# ToneGeneratorSMD_V1viii.net
KiCad netlist of a schematic drawn in EAGLE
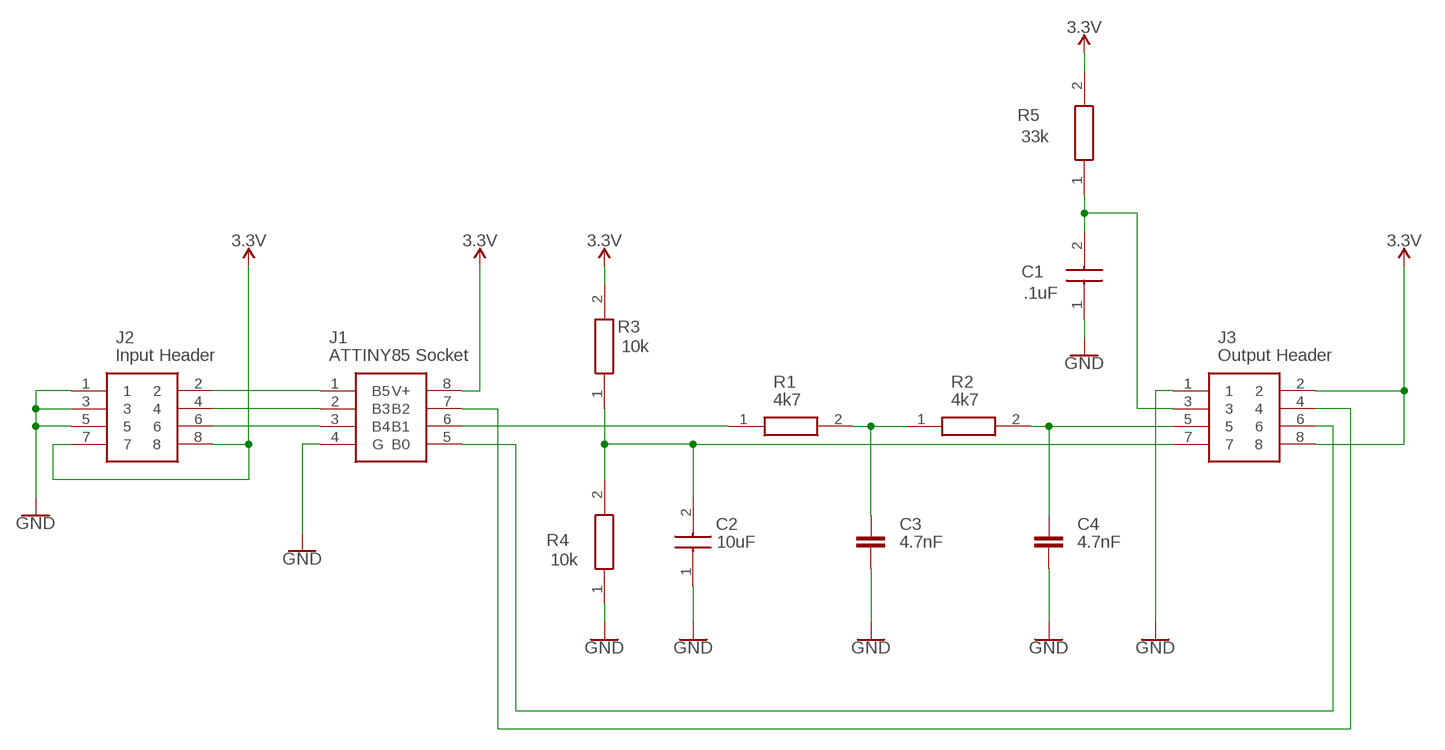
[diagram p0: schematic, sheet 1]

(export (version "E")
  (design (tool "Eeschema 10.0.6"))
  (components
    (comp (ref "C1")
      (value ".1uF")
      (footprint "eagle-import:CAPC2012X90N")
      (fields
        (field (name "MANUFACTURER_PART_NUMBER") "885012207098")
        (field (name "MOUSER_PART_NUMBER") "710-885012207098")
      )
      (libsource (lib "eagle-import") (part "885012207098"))
    )
    (comp (ref "C2")
      (value "10uF")
      (footprint "eagle-import:CAPC2012X145N")
      (fields
        (field (name "MANUFACTURER_PART_NUMBER") "GRM21BR61E106MA73L")
        (field (name "MOUSER_PART_NUMBER") "81-GRM21BR61E106MA3L")
      )
      (libsource (lib "eagle-import") (part "GRM21BR61E106MA73L"))
    )
    (comp (ref "C3")
      (value "4.7nF")
      (footprint "eagle-import:C0805")
      (libsource (lib "eagle-import") (part "C-EUC0805"))
    )
    (comp (ref "C4")
      (value "4.7nF")
      (footprint "eagle-import:C0805")
      (libsource (lib "eagle-import") (part "C-EUC0805"))
    )
    (comp (ref "J1")
      (value "ATTINY85 Socket")
      (footprint "eagle-import:2144430801670800")
      (fields
        (field (name "MANUFACTURER_PART_NUMBER") "214-44-308-01-670800")
        (field (name "MOUSER_PART_NUMBER") "575-4430801")
      )
      (libsource (lib "eagle-import") (part "214-44-308-01-670800"))
    )
    (comp (ref "J2")
      (value "Input Header")
      (footprint "eagle-import:878980826")
      (fields
        (field (name "MANUFACTURER_PART_NUMBER") "87898-0826")
        (field (name "MOUSER_PART_NUMBER") "538-87898-0826")
      )
      (libsource (lib "eagle-import") (part "87898-0826"))
    )
    (comp (ref "J3")
      (value "Output Header")
      (footprint "eagle-import:878980826")
      (fields
        (field (name "MANUFACTURER_PART_NUMBER") "87898-0826")
        (field (name "MOUSER_PART_NUMBER") "538-87898-0826")
      )
      (libsource (lib "eagle-import") (part "87898-0826"))
    )
    (comp (ref "R1")
      (value "4k7")
      (footprint "eagle-import:RESC2013X65N")
      (fields
        (field (name "MANUFACTURER_PART_NUMBER") "ERJ-6GEYJ472V")
        (field (name "MOUSER_PART_NUMBER") "667-ERJ-6GEYJ472V")
      )
      (libsource (lib "eagle-import") (part "ERJ-6GEYJ472V"))
    )
    (comp (ref "R2")
      (value "4k7")
      (footprint "eagle-import:RESC2013X65N")
      (fields
        (field (name "MANUFACTURER_PART_NUMBER") "ERJ-6GEYJ472V")
        (field (name "MOUSER_PART_NUMBER") "667-ERJ-6GEYJ472V")
      )
      (libsource (lib "eagle-import") (part "ERJ-6GEYJ472V"))
    )
    (comp (ref "R3")
      (value "10k")
      (footprint "eagle-import:RESC2013X65N")
      (fields
        (field (name "MANUFACTURER_PART_NUMBER") "ERJ-6GEYJ472V")
        (field (name "MOUSER_PART_NUMBER") "667-ERJ-6GEYJ472V")
      )
      (libsource (lib "eagle-import") (part "ERJ-6GEYJ472V"))
    )
    (comp (ref "R4")
      (value "10k")
      (footprint "eagle-import:RESC2013X65N")
      (fields
        (field (name "MANUFACTURER_PART_NUMBER") "ERJ-6GEYJ472V")
        (field (name "MOUSER_PART_NUMBER") "667-ERJ-6GEYJ472V")
      )
      (libsource (lib "eagle-import") (part "ERJ-6GEYJ472V"))
    )
    (comp (ref "R5")
      (value "33k")
      (footprint "eagle-import:RESC2013X65N")
      (fields
        (field (name "MANUFACTURER_PART_NUMBER") "ERJ-6GEYJ472V")
        (field (name "MOUSER_PART_NUMBER") "667-ERJ-6GEYJ472V")
      )
      (libsource (lib "eagle-import") (part "ERJ-6GEYJ472V"))
    )
  )
  (nets
    (net (code "1") (name "3.3V") (class "Default")
      (node (ref "J1") (pin "8") (pinfunction "V+_8") (pintype "bidirectional"))
      (node (ref "J2") (pin "7") (pinfunction "7_7") (pintype "bidirectional"))
      (node (ref "J2") (pin "8") (pinfunction "8_8") (pintype "bidirectional"))
      (node (ref "J3") (pin "2") (pinfunction "2_2") (pintype "bidirectional"))
      (node (ref "J3") (pin "8") (pinfunction "8_8") (pintype "bidirectional"))
      (node (ref "R3") (pin "2") (pinfunction "R2_2") (pintype "bidirectional"))
      (node (ref "R5") (pin "2") (pinfunction "R2_2") (pintype "bidirectional"))
    )
    (net (code "2") (name "GND") (class "Default")
      (node (ref "C1") (pin "1") (pinfunction "1_1") (pintype "bidirectional"))
      (node (ref "C2") (pin "1") (pinfunction "1_1") (pintype "bidirectional"))
      (node (ref "C3") (pin "2") (pinfunction "2_2") (pintype "passive"))
      (node (ref "C4") (pin "2") (pinfunction "2_2") (pintype "passive"))
      (node (ref "J1") (pin "4") (pinfunction "G_4") (pintype "bidirectional"))
      (node (ref "J2") (pin "1") (pinfunction "1_1") (pintype "bidirectional"))
      (node (ref "J2") (pin "3") (pinfunction "3_3") (pintype "bidirectional"))
      (node (ref "J2") (pin "5") (pinfunction "5_5") (pintype "bidirectional"))
      (node (ref "J3") (pin "1") (pinfunction "1_1") (pintype "bidirectional"))
      (node (ref "R4") (pin "1") (pinfunction "R1_1") (pintype "bidirectional"))
    )
    (net (code "3") (name "Net-(J1-B0)") (class "Default")
      (node (ref "J1") (pin "5") (pinfunction "B0_5") (pintype "bidirectional"))
      (node (ref "J3") (pin "6") (pinfunction "6_6") (pintype "bidirectional"))
    )
    (net (code "4") (name "Net-(J1-B1)") (class "Default")
      (node (ref "J1") (pin "6") (pinfunction "B1_6") (pintype "bidirectional"))
      (node (ref "R1") (pin "1") (pinfunction "R1_1") (pintype "bidirectional"))
    )
    (net (code "5") (name "Net-(J1-B2)") (class "Default")
      (node (ref "J1") (pin "7") (pinfunction "B2_7") (pintype "bidirectional"))
      (node (ref "J3") (pin "4") (pinfunction "4_4") (pintype "bidirectional"))
    )
    (net (code "6") (name "Net-(J1-B3)") (class "Default")
      (node (ref "J1") (pin "2") (pinfunction "B3_2") (pintype "bidirectional"))
      (node (ref "J2") (pin "4") (pinfunction "4_4") (pintype "bidirectional"))
    )
    (net (code "7") (name "Net-(J1-B4)") (class "Default")
      (node (ref "J1") (pin "3") (pinfunction "B4_3") (pintype "bidirectional"))
      (node (ref "J2") (pin "6") (pinfunction "6_6") (pintype "bidirectional"))
    )
    (net (code "8") (name "Net-(J1-B5)") (class "Default")
      (node (ref "J1") (pin "1") (pinfunction "B5_1") (pintype "bidirectional"))
      (node (ref "J2") (pin "2") (pinfunction "2_2") (pintype "bidirectional"))
    )
    (net (code "9") (name "Net-(R1-R2)") (class "Default")
      (node (ref "C3") (pin "1") (pinfunction "1_1") (pintype "passive"))
      (node (ref "R1") (pin "2") (pinfunction "R2_2") (pintype "bidirectional"))
      (node (ref "R2") (pin "1") (pinfunction "R1_1") (pintype "bidirectional"))
    )
    (net (code "10") (name "Net-(R2-R2)") (class "Default")
      (node (ref "C4") (pin "1") (pinfunction "1_1") (pintype "passive"))
      (node (ref "J3") (pin "5") (pinfunction "5_5") (pintype "bidirectional"))
      (node (ref "R2") (pin "2") (pinfunction "R2_2") (pintype "bidirectional"))
    )
    (net (code "11") (name "Net-(R3-R1)") (class "Default")
      (node (ref "C2") (pin "2") (pinfunction "2_2") (pintype "bidirectional"))
      (node (ref "J3") (pin "7") (pinfunction "7_7") (pintype "bidirectional"))
      (node (ref "R3") (pin "1") (pinfunction "R1_1") (pintype "bidirectional"))
      (node (ref "R4") (pin "2") (pinfunction "R2_2") (pintype "bidirectional"))
    )
    (net (code "12") (name "Net-(R5-R1)") (class "Default")
      (node (ref "C1") (pin "2") (pinfunction "2_2") (pintype "bidirectional"))
      (node (ref "J3") (pin "3") (pinfunction "3_3") (pintype "bidirectional"))
      (node (ref "R5") (pin "1") (pinfunction "R1_1") (pintype "bidirectional"))
    )
  )
)
